# MinieasyMySens-v01.net
KiCad netlist of a schematic drawn in EAGLE
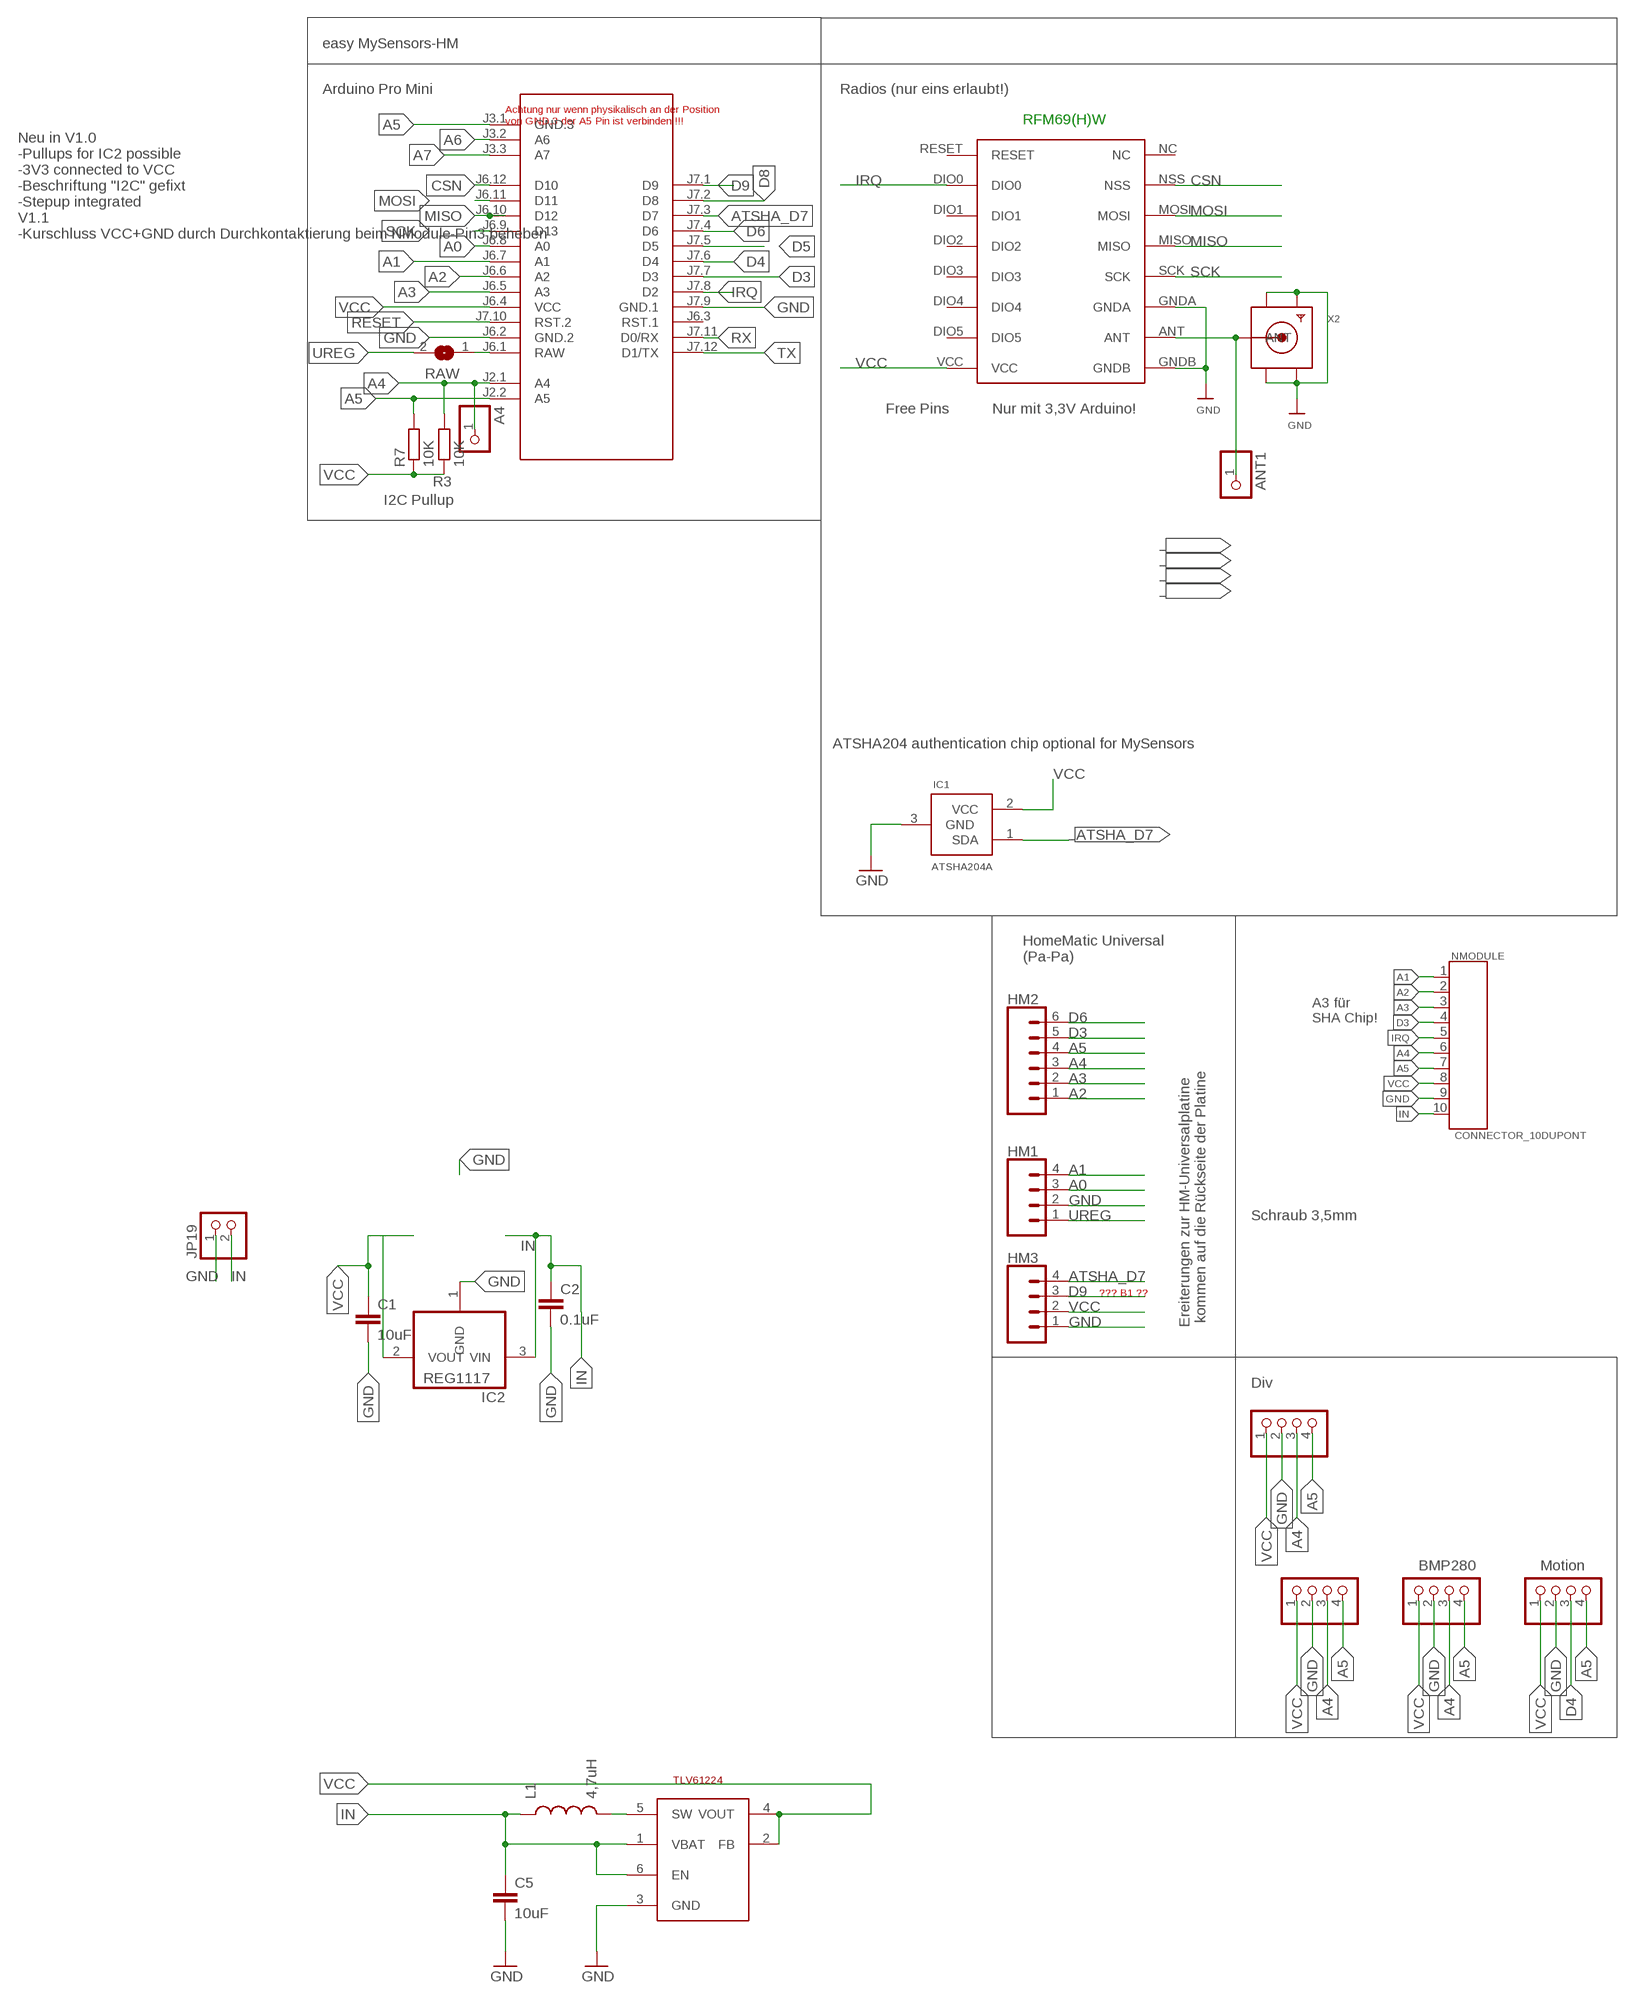
[diagram p0: schematic, sheet 1]

(export (version "E")
  (design (tool "Eeschema 10.0.6"))
  (components
    (comp (ref "A4")
      (value "PINHD-1X1")
      (footprint "eagle-import:1X01")
      (libsource (lib "eagle-import") (part "PINHD-1X1"))
    )
    (comp (ref "ANT1")
      (value "PINHD-1X1")
      (footprint "eagle-import:1X01")
      (libsource (lib "eagle-import") (part "PINHD-1X1"))
    )
    (comp (ref "BH1750")
      (value "PINHD-1X04_2.54-S")
      (footprint "eagle-import:1X04-S")
      (libsource (lib "eagle-import") (part "PINHD-1X04_2.54-S"))
    )
    (comp (ref "C1")
      (value "10uF")
      (footprint "eagle-import:C1210")
      (libsource (lib "eagle-import") (part "C-EUC1210"))
    )
    (comp (ref "C2")
      (value "0.1uF")
      (footprint "eagle-import:C1206")
      (libsource (lib "eagle-import") (part "C-EUC1206"))
    )
    (comp (ref "C5")
      (value "10uF")
      (footprint "eagle-import:0805")
      (libsource (lib "eagle-import") (part "CAP0805"))
    )
    (comp (ref "HM1")
      (value "CONN_04")
      (footprint "eagle-import:1X04")
      (libsource (lib "eagle-import") (part "CONN_04"))
    )
    (comp (ref "HM2")
      (value "CONN_06SILK_FEMALE_PTH")
      (footprint "eagle-import:1X06")
      (libsource (lib "eagle-import") (part "CONN_06SILK_FEMALE_PTH"))
    )
    (comp (ref "HM3")
      (value "CONN_04")
      (footprint "eagle-import:1X04")
      (libsource (lib "eagle-import") (part "CONN_04"))
    )
    (comp (ref "I2C-1")
      (value "PINHD-1X04_2.54-S")
      (footprint "eagle-import:1X04-S")
      (libsource (lib "eagle-import") (part "PINHD-1X04_2.54-S"))
    )
    (comp (ref "I2C-2")
      (value "PINHD-1X04_2.54-S")
      (footprint "eagle-import:1X04-S")
      (libsource (lib "eagle-import") (part "PINHD-1X04_2.54-S"))
    )
    (comp (ref "IC1")
      (value "ATSHA204A")
      (footprint "eagle-import:SOT23")
      (libsource (lib "eagle-import") (part "ATSHA204A"))
    )
    (comp (ref "IC2")
      (value "REG1117")
      (footprint "eagle-import:SOT223")
      (libsource (lib "eagle-import") (part "REG1117"))
    )
    (comp (ref "JP19")
      (value "PINHD-1X2")
      (footprint "eagle-import:1X02")
      (libsource (lib "eagle-import") (part "PINHD-1X2"))
    )
    (comp (ref "L1")
      (value "4,7uH")
      (footprint "eagle-import:0805")
      (libsource (lib "eagle-import") (part "INDUCTOR0805"))
    )
    (comp (ref "M1")
      (value "ARDUINO-PRO-MINI-3.3V#NP")
      (footprint "eagle-import:ARDUINO-PRO-MINI#NP")
      (libsource (lib "eagle-import") (part "ARDUINO-PRO-MINI-#NP3.3V"))
    )
    (comp (ref "MOTION")
      (value "PINHD-1X04_2.54-S")
      (footprint "eagle-import:1X04-S")
      (libsource (lib "eagle-import") (part "PINHD-1X04_2.54-S"))
    )
    (comp (ref "NMODULE")
      (value "CONNECTOR_10DUPONT")
      (footprint "eagle-import:DUPONT_10")
      (libsource (lib "eagle-import") (part "CONNECTOR_10DUPONT"))
    )
    (comp (ref "R3")
      (value "10K")
      (footprint "eagle-import:R0805")
      (libsource (lib "eagle-import") (part "R-EU_R0805"))
    )
    (comp (ref "R7")
      (value "10K")
      (footprint "eagle-import:R0805")
      (libsource (lib "eagle-import") (part "R-EU_R0805"))
    )
    (comp (ref "RAW") (value "SJ") (footprint "eagle-import:SJ") (libsource (lib "eagle-import") (part "SJ")))
    (comp (ref "RFM69W")
      (value "RFM69HW")
      (footprint "eagle-import:RFM")
      (libsource (lib "eagle-import") (part "RFM69HW"))
    )
    (comp (ref "STEPUP")
      (value "TLV61224")
      (footprint "eagle-import:SOT23-6L")
      (libsource (lib "eagle-import") (part "TI-TLV61224"))
    )
    (comp (ref "X2")
      (value "SMACONNECTOR_EDGE")
      (footprint "eagle-import:SMA_EDGELAUNCH")
      (libsource (lib "eagle-import") (part "SMACONNECTOR_EDGE"))
    )
  )
  (nets
    (net (code "1") (name "A0") (class "Default")
      (node (ref "HM1") (pin "3") (pinfunction "3_3") (pintype "passive"))
      (node (ref "M1") (pin "J6.8") (pinfunction "A0_J6.8") (pintype "bidirectional"))
    )
    (net (code "2") (name "A1") (class "Default")
      (node (ref "HM1") (pin "4") (pinfunction "4_4") (pintype "passive"))
      (node (ref "M1") (pin "J6.7") (pinfunction "A1_J6.7") (pintype "bidirectional"))
      (node (ref "NMODULE") (pin "1") (pinfunction "1_1") (pintype "bidirectional"))
    )
    (net (code "3") (name "A2") (class "Default")
      (node (ref "HM2") (pin "1") (pinfunction "1_1") (pintype "passive"))
      (node (ref "M1") (pin "J6.6") (pinfunction "A2_J6.6") (pintype "bidirectional"))
      (node (ref "NMODULE") (pin "2") (pinfunction "2_2") (pintype "bidirectional"))
    )
    (net (code "4") (name "A3") (class "Default")
      (node (ref "HM2") (pin "2") (pinfunction "2_2") (pintype "passive"))
      (node (ref "M1") (pin "J6.5") (pinfunction "A3_J6.5") (pintype "bidirectional"))
      (node (ref "NMODULE") (pin "3") (pinfunction "3_3") (pintype "bidirectional"))
    )
    (net (code "5") (name "A4") (class "Default")
      (node (ref "A4") (pin "1") (pinfunction "1_1") (pintype "passive"))
      (node (ref "BH1750") (pin "3") (pinfunction "3_3") (pintype "passive"))
      (node (ref "HM2") (pin "3") (pinfunction "3_3") (pintype "passive"))
      (node (ref "I2C-1") (pin "3") (pinfunction "3_3") (pintype "passive"))
      (node (ref "I2C-2") (pin "3") (pinfunction "3_3") (pintype "passive"))
      (node (ref "M1") (pin "J2.1") (pinfunction "A4_J2.1") (pintype "bidirectional"))
      (node (ref "NMODULE") (pin "6") (pinfunction "6_6") (pintype "bidirectional"))
      (node (ref "R3") (pin "2") (pinfunction "2_2") (pintype "passive"))
    )
    (net (code "6") (name "A5") (class "Default")
      (node (ref "BH1750") (pin "4") (pinfunction "4_4") (pintype "passive"))
      (node (ref "HM2") (pin "4") (pinfunction "4_4") (pintype "passive"))
      (node (ref "I2C-1") (pin "4") (pinfunction "4_4") (pintype "passive"))
      (node (ref "I2C-2") (pin "4") (pinfunction "4_4") (pintype "passive"))
      (node (ref "M1") (pin "J2.2") (pinfunction "A5_J2.2") (pintype "bidirectional"))
      (node (ref "M1") (pin "J3.1") (pinfunction "GND.3_J3.1") (pintype "bidirectional"))
      (node (ref "MOTION") (pin "4") (pinfunction "4_4") (pintype "passive"))
      (node (ref "NMODULE") (pin "7") (pinfunction "7_7") (pintype "bidirectional"))
      (node (ref "R7") (pin "2") (pinfunction "2_2") (pintype "passive"))
    )
    (net (code "7") (name "A6") (class "Default")
      (node (ref "M1") (pin "J3.2") (pinfunction "A6_J3.2") (pintype "bidirectional"))
    )
    (net (code "8") (name "A7") (class "Default")
      (node (ref "M1") (pin "J3.3") (pinfunction "A7_J3.3") (pintype "bidirectional"))
    )
    (net (code "9") (name "ATSHA_D7") (class "Default")
      (node (ref "HM3") (pin "4") (pinfunction "4_4") (pintype "passive"))
      (node (ref "IC1") (pin "1") (pinfunction "SDA_1") (pintype "bidirectional"))
      (node (ref "M1") (pin "J7.3") (pinfunction "D7_J7.3") (pintype "bidirectional"))
    )
    (net (code "10") (name "CSN") (class "Default")
      (node (ref "M1") (pin "J6.12") (pinfunction "D10_J6.12") (pintype "bidirectional"))
      (node (ref "RFM69W") (pin "NSS") (pinfunction "NSS_NSS") (pintype "bidirectional"))
    )
    (net (code "11") (name "D3") (class "Default")
      (node (ref "HM2") (pin "5") (pinfunction "5_5") (pintype "passive"))
      (node (ref "M1") (pin "J7.7") (pinfunction "D3_J7.7") (pintype "bidirectional"))
      (node (ref "NMODULE") (pin "4") (pinfunction "4_4") (pintype "bidirectional"))
    )
    (net (code "12") (name "D4") (class "Default")
      (node (ref "M1") (pin "J7.6") (pinfunction "D4_J7.6") (pintype "bidirectional"))
      (node (ref "MOTION") (pin "3") (pinfunction "3_3") (pintype "passive"))
    )
    (net (code "13") (name "D5") (class "Default")
      (node (ref "M1") (pin "J7.5") (pinfunction "D5_J7.5") (pintype "bidirectional"))
    )
    (net (code "14") (name "D6") (class "Default")
      (node (ref "HM2") (pin "6") (pinfunction "6_6") (pintype "passive"))
      (node (ref "M1") (pin "J7.4") (pinfunction "D6_J7.4") (pintype "bidirectional"))
    )
    (net (code "15") (name "D8") (class "Default")
      (node (ref "M1") (pin "J7.2") (pinfunction "D8_J7.2") (pintype "bidirectional"))
    )
    (net (code "16") (name "D9") (class "Default")
      (node (ref "HM3") (pin "3") (pinfunction "3_3") (pintype "passive"))
      (node (ref "M1") (pin "J7.1") (pinfunction "D9_J7.1") (pintype "bidirectional"))
    )
    (net (code "17") (name "GND") (class "Default")
      (node (ref "BH1750") (pin "2") (pinfunction "2_2") (pintype "passive"))
      (node (ref "C1") (pin "2") (pinfunction "2_2") (pintype "passive"))
      (node (ref "C2") (pin "2") (pinfunction "2_2") (pintype "passive"))
      (node (ref "C5") (pin "2") (pinfunction "2_2") (pintype "passive"))
      (node (ref "HM1") (pin "2") (pinfunction "2_2") (pintype "passive"))
      (node (ref "HM3") (pin "1") (pinfunction "1_1") (pintype "passive"))
      (node (ref "I2C-1") (pin "2") (pinfunction "2_2") (pintype "passive"))
      (node (ref "I2C-2") (pin "2") (pinfunction "2_2") (pintype "passive"))
      (node (ref "IC1") (pin "3") (pinfunction "GND_3") (pintype "bidirectional"))
      (node (ref "IC2") (pin "1") (pinfunction "GND_1") (pintype "power_in"))
      (node (ref "JP19") (pin "1") (pinfunction "1_1") (pintype "passive"))
      (node (ref "M1") (pin "J6.2") (pinfunction "GND.2_J6.2") (pintype "power_in"))
      (node (ref "M1") (pin "J7.9") (pinfunction "GND.1_J7.9") (pintype "power_in"))
      (node (ref "MOTION") (pin "2") (pinfunction "2_2") (pintype "passive"))
      (node (ref "NMODULE") (pin "9") (pinfunction "9_9") (pintype "bidirectional"))
      (node (ref "RFM69W") (pin "GNDA") (pinfunction "GNDA_GNDA") (pintype "bidirectional"))
      (node (ref "RFM69W") (pin "GNDB") (pinfunction "GNDB_GNDB") (pintype "bidirectional"))
      (node (ref "STEPUP") (pin "3") (pinfunction "GND_3") (pintype "power_in"))
      (node (ref "X2") (pin "GND@1") (pinfunction "GND4_GND@1") (pintype "power_in"))
      (node (ref "X2") (pin "GND@2") (pinfunction "GND3_GND@2") (pintype "power_in"))
      (node (ref "X2") (pin "GND@3") (pinfunction "GND2_GND@3") (pintype "power_in"))
      (node (ref "X2") (pin "GND@4") (pinfunction "GND1_GND@4") (pintype "power_in"))
    )
    (net (code "18") (name "IN") (class "Default")
      (node (ref "C2") (pin "1") (pinfunction "1_1") (pintype "passive"))
      (node (ref "C5") (pin "1") (pinfunction "1_1") (pintype "passive"))
      (node (ref "IC2") (pin "3") (pinfunction "VIN_3") (pintype "input"))
      (node (ref "JP19") (pin "2") (pinfunction "2_2") (pintype "passive"))
      (node (ref "L1") (pin "1") (pinfunction "1_1") (pintype "passive"))
      (node (ref "NMODULE") (pin "10") (pinfunction "10_10") (pintype "bidirectional"))
      (node (ref "STEPUP") (pin "1") (pinfunction "VBAT_1") (pintype "power_in"))
      (node (ref "STEPUP") (pin "6") (pinfunction "EN_6") (pintype "input"))
    )
    (net (code "19") (name "IRQ") (class "Default")
      (node (ref "M1") (pin "J7.8") (pinfunction "D2_J7.8") (pintype "bidirectional"))
      (node (ref "NMODULE") (pin "5") (pinfunction "5_5") (pintype "bidirectional"))
      (node (ref "RFM69W") (pin "DIO0") (pinfunction "DIO0_DIO0") (pintype "bidirectional"))
    )
    (net (code "20") (name "MISO") (class "Default")
      (node (ref "M1") (pin "J6.10") (pinfunction "D12_J6.10") (pintype "bidirectional"))
      (node (ref "RFM69W") (pin "MISO") (pinfunction "MISO_MISO") (pintype "bidirectional"))
    )
    (net (code "21") (name "MOSI") (class "Default")
      (node (ref "M1") (pin "J6.11") (pinfunction "D11_J6.11") (pintype "bidirectional"))
      (node (ref "RFM69W") (pin "MOSI") (pinfunction "MOSI_MOSI") (pintype "bidirectional"))
    )
    (net (code "22") (name "Net-(M1-RAW)") (class "Default")
      (node (ref "M1") (pin "J6.1") (pinfunction "RAW_J6.1") (pintype "power_in"))
      (node (ref "RAW") (pin "1") (pinfunction "1_1") (pintype "passive"))
    )
    (net (code "23") (name "Net-(STEPUP-SW)") (class "Default")
      (node (ref "L1") (pin "2") (pinfunction "2_2") (pintype "passive"))
      (node (ref "STEPUP") (pin "5") (pinfunction "SW_5") (pintype "power_in"))
    )
    (net (code "24") (name "Net-(X2-ANT)") (class "Default")
      (node (ref "ANT1") (pin "1") (pinfunction "1_1") (pintype "passive"))
      (node (ref "RFM69W") (pin "ANT") (pinfunction "ANT_ANT") (pintype "bidirectional"))
      (node (ref "X2") (pin "P") (pinfunction "ANT_P") (pintype "bidirectional"))
    )
    (net (code "25") (name "RESET") (class "Default")
      (node (ref "M1") (pin "J7.10") (pinfunction "RST.2_J7.10") (pintype "bidirectional"))
    )
    (net (code "26") (name "RX") (class "Default")
      (node (ref "M1") (pin "J7.11") (pinfunction "D0/RX_J7.11") (pintype "bidirectional"))
    )
    (net (code "27") (name "SCK") (class "Default")
      (node (ref "M1") (pin "J6.9") (pinfunction "D13_J6.9") (pintype "bidirectional"))
      (node (ref "RFM69W") (pin "SCK") (pinfunction "SCK_SCK") (pintype "bidirectional"))
    )
    (net (code "28") (name "TX") (class "Default")
      (node (ref "M1") (pin "J7.12") (pinfunction "D1/TX_J7.12") (pintype "bidirectional"))
    )
    (net (code "29") (name "UREG") (class "Default")
      (node (ref "HM1") (pin "1") (pinfunction "1_1") (pintype "passive"))
      (node (ref "RAW") (pin "2") (pinfunction "2_2") (pintype "passive"))
    )
    (net (code "30") (name "VCC") (class "Default")
      (node (ref "BH1750") (pin "1") (pinfunction "1_1") (pintype "passive"))
      (node (ref "C1") (pin "1") (pinfunction "1_1") (pintype "passive"))
      (node (ref "HM3") (pin "2") (pinfunction "2_2") (pintype "passive"))
      (node (ref "I2C-1") (pin "1") (pinfunction "1_1") (pintype "passive"))
      (node (ref "I2C-2") (pin "1") (pinfunction "1_1") (pintype "passive"))
      (node (ref "IC1") (pin "2") (pinfunction "VCC_2") (pintype "bidirectional"))
      (node (ref "IC2") (pin "2") (pinfunction "VOUT_2") (pintype "output"))
      (node (ref "M1") (pin "J6.4") (pinfunction "VCC_J6.4") (pintype "power_in"))
      (node (ref "MOTION") (pin "1") (pinfunction "1_1") (pintype "passive"))
      (node (ref "NMODULE") (pin "8") (pinfunction "8_8") (pintype "bidirectional"))
      (node (ref "R3") (pin "1") (pinfunction "1_1") (pintype "passive"))
      (node (ref "R7") (pin "1") (pinfunction "1_1") (pintype "passive"))
      (node (ref "RFM69W") (pin "VCC") (pinfunction "VCC_VCC") (pintype "bidirectional"))
      (node (ref "STEPUP") (pin "2") (pinfunction "FB_2") (pintype "input"))
      (node (ref "STEPUP") (pin "4") (pinfunction "VOUT_4") (pintype "power_in"))
    )
    (net (code "31") (name "unconnected-(M1-RST.1-PadJ6.3)") (class "Default")
      (node (ref "M1") (pin "J6.3") (pinfunction "RST.1_J6.3") (pintype "bidirectional"))
    )
    (net (code "32") (name "unconnected-(RFM69W-PadDIO1)") (class "Default")
      (node (ref "RFM69W") (pin "DIO1") (pinfunction "DIO1_DIO1") (pintype "bidirectional"))
    )
    (net (code "33") (name "unconnected-(RFM69W-PadDIO2)") (class "Default")
      (node (ref "RFM69W") (pin "DIO2") (pinfunction "DIO2_DIO2") (pintype "bidirectional"))
    )
    (net (code "34") (name "unconnected-(RFM69W-PadDIO3)") (class "Default")
      (node (ref "RFM69W") (pin "DIO3") (pinfunction "DIO3_DIO3") (pintype "bidirectional"))
    )
    (net (code "35") (name "unconnected-(RFM69W-PadDIO4)") (class "Default")
      (node (ref "RFM69W") (pin "DIO4") (pinfunction "DIO4_DIO4") (pintype "bidirectional"))
    )
    (net (code "36") (name "unconnected-(RFM69W-PadDIO5)") (class "Default")
      (node (ref "RFM69W") (pin "DIO5") (pinfunction "DIO5_DIO5") (pintype "bidirectional"))
    )
    (net (code "37") (name "unconnected-(RFM69W-PadNC)") (class "Default")
      (node (ref "RFM69W") (pin "NC") (pinfunction "NC_NC") (pintype "bidirectional"))
    )
    (net (code "38") (name "unconnected-(RFM69W-PadRESET)") (class "Default")
      (node (ref "RFM69W") (pin "RESET") (pinfunction "RESET_RESET") (pintype "bidirectional"))
    )
  )
)
